# StepperV2.net
KiCad netlist of a schematic drawn in Altium Designer
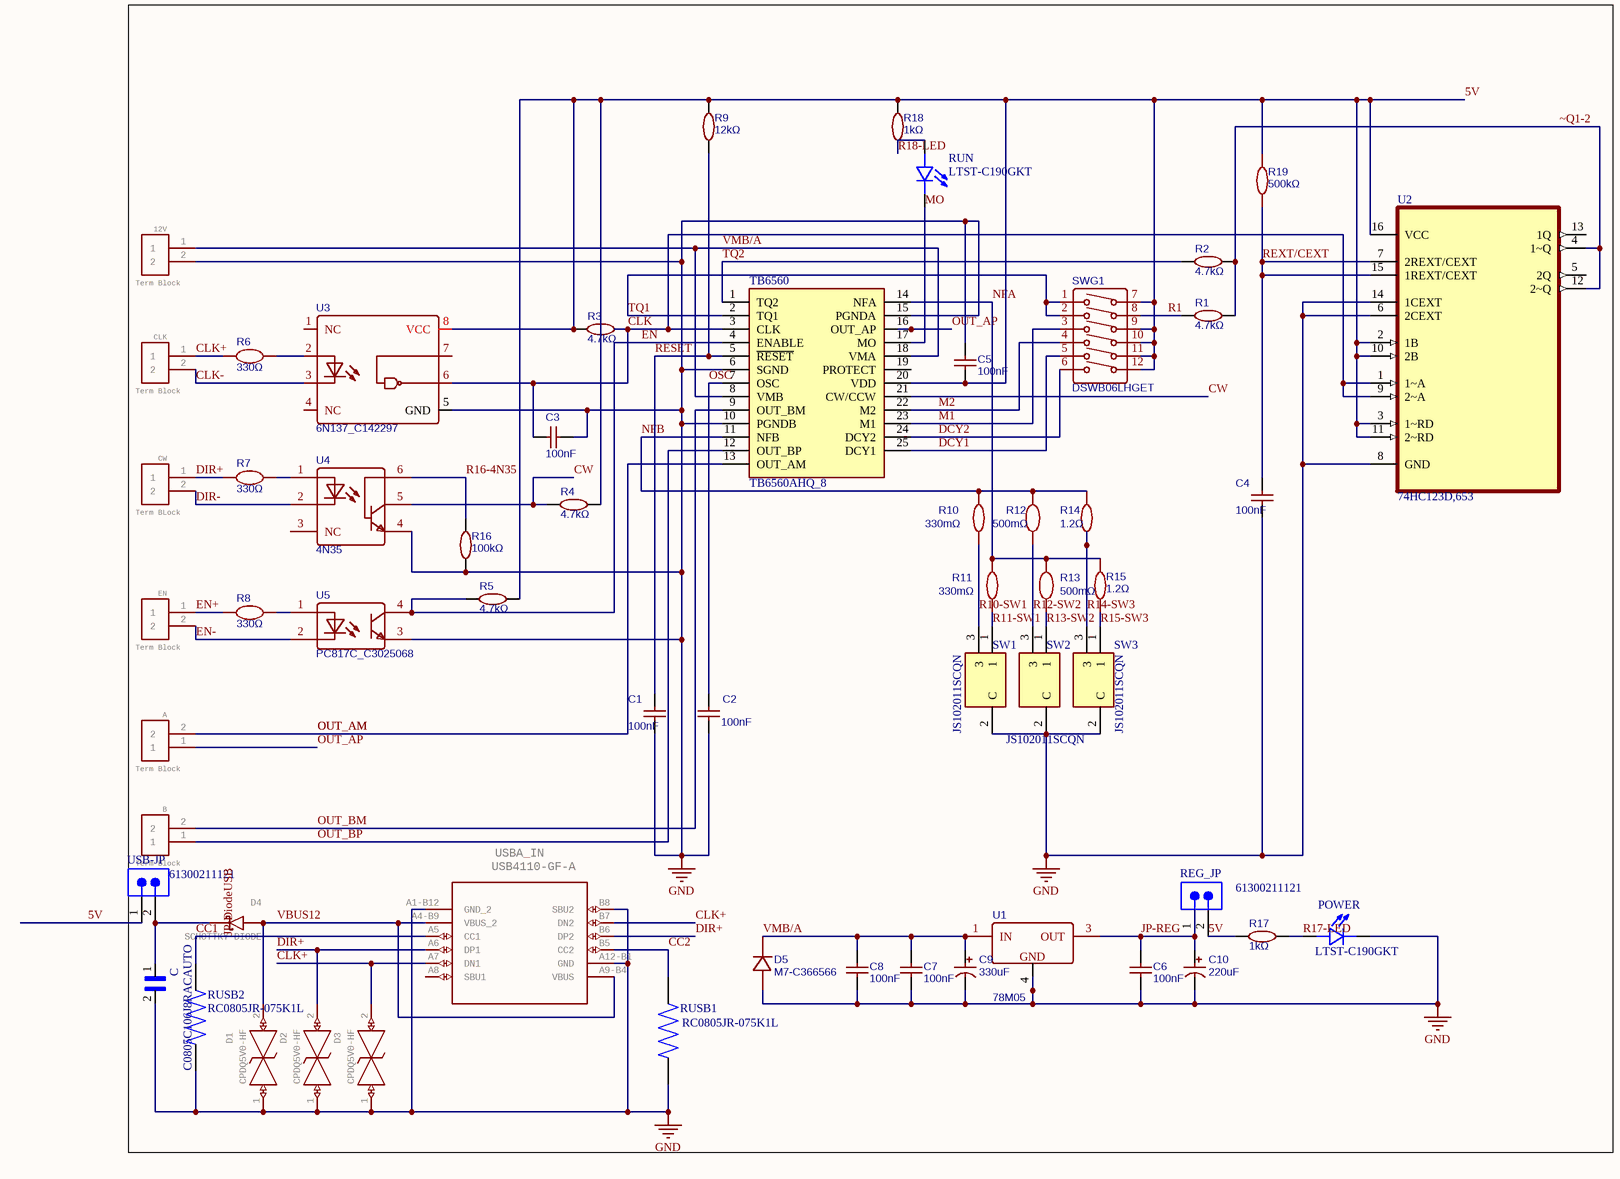
[diagram p0: StepperV2.SchDoc]

(export (version "E")
  (design (tool "Eeschema 10.0.6"))
  (components
    (comp (ref "12V")
      (value "Term Block")
      (footprint "TE_282837-2")
      (fields (field (name "MF") "TE Connectivity") (field (name "MP") "282837-2"))
      (libsource (lib "Terminal_Block2P") (part "282837-2"))
    )
    (comp (ref "A")
      (value "Term Block")
      (footprint "TE_282837-2")
      (fields (field (name "MF") "TE Connectivity") (field (name "MP") "282837-2"))
      (libsource (lib "") (part "282837-2_1"))
    )
    (comp (ref "B")
      (value "Term Block")
      (footprint "TE_282837-2")
      (fields (field (name "MF") "TE Connectivity") (field (name "MP") "282837-2"))
      (libsource (lib "Terminal_Block2P") (part "282837-2"))
    )
    (comp (ref "C")
      (value "C0805C106J8RACAUTO")
      (footprint "C0805C106J8RACAUTO.:CAPC2012X88N")
      (description "10ÂµF Â±5% 10V Ceramic Capacitor X7R 0805 _2012 Metric_")
      (fields (field (name "MF") "KEMET"))
      (libsource (lib "C0805C106J8RACAUTO") (part "C0805C106J8RACAUTO"))
    )
    (comp (ref "C1")
      (value "100nF")
      (footprint "C0805")
      (fields (field (name "MANUFACTURER") "FH(风华)") (field (name "MANUFACTURER PART") "0805B104J500NT"))
      (libsource (lib "0.1uFCAP") (part "100nF"))
    )
    (comp (ref "C2")
      (value "100nF")
      (footprint "C0805")
      (fields (field (name "MANUFACTURER") "FH(风华)") (field (name "MANUFACTURER PART") "0805B104J500NT"))
      (libsource (lib "0.1uFCAP") (part "100nF"))
    )
    (comp (ref "C3")
      (value "100nF")
      (footprint "C0805")
      (fields (field (name "MANUFACTURER") "FH(风华)") (field (name "MANUFACTURER PART") "0805B104J500NT"))
      (libsource (lib "0.1uFCAP") (part "100nF"))
    )
    (comp (ref "C4")
      (value "100nF")
      (footprint "C0805")
      (fields (field (name "MANUFACTURER") "FH(风华)") (field (name "MANUFACTURER PART") "0805B104J500NT"))
      (libsource (lib "0.1uFCAP") (part "100nF"))
    )
    (comp (ref "C5")
      (value "100nF")
      (footprint "C0805")
      (fields (field (name "MANUFACTURER") "FH(风华)") (field (name "MANUFACTURER PART") "0805B104J500NT"))
      (libsource (lib "0.1uFCAP") (part "100nF"))
    )
    (comp (ref "C6")
      (value "100nF")
      (footprint "C0805")
      (fields (field (name "MANUFACTURER") "FH(风华)") (field (name "MANUFACTURER PART") "0805B104J500NT"))
      (libsource (lib "0.1uFCAP") (part "100nF"))
    )
    (comp (ref "C7")
      (value "100nF")
      (footprint "C0805")
      (fields (field (name "MANUFACTURER") "FH(风华)") (field (name "MANUFACTURER PART") "0805B104J500NT"))
      (libsource (lib "0.1uFCAP") (part "100nF"))
    )
    (comp (ref "C8")
      (value "100nF")
      (footprint "C0805")
      (fields (field (name "MANUFACTURER") "FH(风华)") (field (name "MANUFACTURER PART") "0805B104J500NT"))
      (libsource (lib "0.1uFCAP") (part "100nF"))
    )
    (comp (ref "C9")
      (value "330uF")
      (footprint "CAP-TH_BD8.0-P3.50-D0.6-FD")
      (fields
        (field (name "MANUFACTURER") "CX(承兴)")
        (field (name "MANUFACTURER PART") "GR337M050F20RR0VL4FP0")
      )
      (libsource (lib "330uF_CAP") (part "330uF"))
    )
    (comp (ref "C10")
      (value "220uF")
      (footprint "CAP-TH_BD6.3-P2.50-D1.0-FD")
      (fields
        (field (name "MANUFACTURER") "CX(承兴)")
        (field (name "MANUFACTURER PART") "KM227M016E11RR0VH2FP0")
      )
      (libsource (lib "220uF_CAP") (part "220uF"))
    )
    (comp (ref "CLK")
      (value "Term Block")
      (footprint "TE_282837-2")
      (fields (field (name "MF") "TE Connectivity") (field (name "MP") "282837-2"))
      (libsource (lib "Terminal_Block2P") (part "282837-2"))
    )
    (comp (ref "CW")
      (value "Term BLock")
      (footprint "TE_282837-2")
      (fields (field (name "MF") "TE Connectivity") (field (name "MP") "282837-2"))
      (libsource (lib "Terminal_Block2P") (part "282837-2"))
    )
    (comp (ref "D1")
      (value "CPDQ5V0-HF")
      (footprint "MBTB-D-SOD-923F-IMP-0402")
      (fields (field (name "MF") "Comchip Technology"))
      (libsource (lib "CPDQ5V0-HF") (part "CPDQ5V0-HF"))
    )
    (comp (ref "D2")
      (value "CPDQ5V0-HF")
      (footprint "MBTB-D-SOD-923F-IMP-0402")
      (fields (field (name "MF") "Comchip Technology"))
      (libsource (lib "CPDQ5V0-HF") (part "CPDQ5V0-HF"))
    )
    (comp (ref "D3")
      (value "CPDQ5V0-HF")
      (footprint "MBTB-D-SOD-923F-IMP-0402")
      (fields (field (name "MF") "Comchip Technology"))
      (libsource (lib "CPDQ5V0-HF") (part "CPDQ5V0-HF"))
    )
    (comp (ref "D4")
      (value "SCHOTTKY DIODE")
      (footprint "SOD3715X145N")
      (fields (field (name "MF") "Diodes Inc.") (field (name "MP") "1N5819HW-7-F"))
      (libsource (lib "1N5819HW-7-F") (part "1N5819HW-7-F"))
    )
    (comp (ref "D5")
      (value "M7-C366566")
      (footprint "SMAF_L3.5-W2.6-LS4.7-RD")
      (fields
        (field (name "MANUFACTURER") "DOWO(东沃)")
        (field (name "MANUFACTURER PART") "M7")
        (field (name "CONTRIBUTOR") "LCSC")
      )
      (libsource (lib "M7") (part "M7-C366566"))
    )
    (comp (ref "EN")
      (value "Term Block")
      (footprint "TE_282837-2")
      (fields (field (name "MF") "TE Connectivity") (field (name "MP") "282837-2"))
      (libsource (lib "Terminal_Block2P") (part "282837-2"))
    )
    (comp (ref "POWER")
      (value "LTST-C190GKT")
      (footprint "LEDC1608X35N")
      (fields (field (name "MF") "{'manufacturer': u'Lite-On Inc.'}"))
      (libsource (lib "") (part "LTST-C190GKT_1"))
    )
    (comp (ref "R1")
      (value "4.7kΩ")
      (footprint "R0805")
      (fields (field (name "MANUFACTURER") "FH(风华)") (field (name "MANUFACTURER PART") "RS-05K472JT"))
      (libsource (lib "4_7KO") (part "4.7kΩ"))
    )
    (comp (ref "R2")
      (value "4.7kΩ")
      (footprint "R0805")
      (fields (field (name "MANUFACTURER") "FH(风华)") (field (name "MANUFACTURER PART") "RS-05K472JT"))
      (libsource (lib "4_7KO") (part "4.7kΩ"))
    )
    (comp (ref "R3")
      (value "4.7kΩ")
      (footprint "R0805")
      (fields (field (name "MANUFACTURER") "FH(风华)") (field (name "MANUFACTURER PART") "RS-05K472JT"))
      (libsource (lib "4_7KO") (part "4.7kΩ"))
    )
    (comp (ref "R4")
      (value "4.7kΩ")
      (footprint "R0805")
      (fields (field (name "MANUFACTURER") "FH(风华)") (field (name "MANUFACTURER PART") "RS-05K472JT"))
      (libsource (lib "4_7KO") (part "4.7kΩ"))
    )
    (comp (ref "R5")
      (value "4.7kΩ")
      (footprint "R0805")
      (fields (field (name "MANUFACTURER") "FH(风华)") (field (name "MANUFACTURER PART") "RS-05K472JT"))
      (libsource (lib "4_7KO") (part "4.7kΩ"))
    )
    (comp (ref "R6")
      (value "330Ω")
      (footprint "R0805")
      (fields
        (field (name "MANUFACTURER") "EVER OHMS(天二科技)")
        (field (name "MANUFACTURER PART") "CR0805J330RP05Z")
        (field (name "CONTRIBUTOR") "LCSC")
      )
      (libsource (lib "330OHM") (part "330Ω"))
    )
    (comp (ref "R7")
      (value "330Ω")
      (footprint "R0805")
      (fields
        (field (name "MANUFACTURER") "EVER OHMS(天二科技)")
        (field (name "MANUFACTURER PART") "CR0805J330RP05Z")
        (field (name "CONTRIBUTOR") "LCSC")
      )
      (libsource (lib "330OHM") (part "330Ω"))
    )
    (comp (ref "R8")
      (value "330Ω")
      (footprint "R0805")
      (fields
        (field (name "MANUFACTURER") "EVER OHMS(天二科技)")
        (field (name "MANUFACTURER PART") "CR0805J330RP05Z")
        (field (name "CONTRIBUTOR") "LCSC")
      )
      (libsource (lib "330OHM") (part "330Ω"))
    )
    (comp (ref "R9")
      (value "12kΩ")
      (footprint "R0805")
      (fields
        (field (name "MANUFACTURER") "UNI-ROYAL(厚声)")
        (field (name "MANUFACTURER PART") "0805W8J0123T5E")
      )
      (libsource (lib "12kOHM") (part "12kΩ"))
    )
    (comp (ref "R10")
      (value "330mΩ")
      (footprint "R2512")
      (fields
        (field (name "MANUFACTURER") "EVER OHMS(天二科技)")
        (field (name "MANUFACTURER PART") "CRH2512JR330E04Z")
        (field (name "CONTRIBUTOR") "LCSC")
      )
      (libsource (lib "0_33OHM") (part "330mΩ"))
    )
    (comp (ref "R11")
      (value "330mΩ")
      (footprint "R2512")
      (fields
        (field (name "MANUFACTURER") "EVER OHMS(天二科技)")
        (field (name "MANUFACTURER PART") "CRH2512JR330E04Z")
        (field (name "CONTRIBUTOR") "LCSC")
      )
      (libsource (lib "0_33OHM") (part "330mΩ"))
    )
    (comp (ref "R12")
      (value "500mΩ")
      (footprint "R2512")
      (fields
        (field (name "MANUFACTURER") "SEI(Stackpole Electronics Inc.)")
        (field (name "MANUFACTURER PART") "CSRN2512FKR500")
        (field (name "CONTRIBUTOR") "LCSC")
      )
      (libsource (lib "0_5OHM") (part "500mΩ"))
    )
    (comp (ref "R13")
      (value "500mΩ")
      (footprint "R2512")
      (fields
        (field (name "MANUFACTURER") "SEI(Stackpole Electronics Inc.)")
        (field (name "MANUFACTURER PART") "CSRN2512FKR500")
        (field (name "CONTRIBUTOR") "LCSC")
      )
      (libsource (lib "0_5OHM") (part "500mΩ"))
    )
    (comp (ref "R14")
      (value "1.2Ω")
      (footprint "R1210")
      (fields
        (field (name "MANUFACTURER") "EVER OHMS(天二科技)")
        (field (name "MANUFACTURER PART") "CR1210F1R20P05S")
        (field (name "CONTRIBUTOR") "LCSC")
      )
      (libsource (lib "1_2OHM") (part "1.2Ω"))
    )
    (comp (ref "R15")
      (value "1.2Ω")
      (footprint "R1210")
      (fields
        (field (name "MANUFACTURER") "EVER OHMS(天二科技)")
        (field (name "MANUFACTURER PART") "CR1210F1R20P05S")
        (field (name "CONTRIBUTOR") "LCSC")
      )
      (libsource (lib "1_2OHM") (part "1.2Ω"))
    )
    (comp (ref "R16")
      (value "100kΩ")
      (footprint "R0805")
      (fields (field (name "MANUFACTURER") "RALEC(旺诠)") (field (name "MANUFACTURER PART") "RTT05104JTP"))
      (libsource (lib "100KOHM") (part "100kΩ"))
    )
    (comp (ref "R17")
      (value "1kΩ")
      (footprint "R0805")
      (fields (field (name "MANUFACTURER") "YAGEO(国巨)") (field (name "MANUFACTURER PART") "RC0805JR-071KL"))
      (libsource (lib "1kOHM") (part "1kΩ"))
    )
    (comp (ref "R18")
      (value "1kΩ")
      (footprint "R0805")
      (fields (field (name "MANUFACTURER") "YAGEO(国巨)") (field (name "MANUFACTURER PART") "RC0805JR-071KL"))
      (libsource (lib "1kOHM") (part "1kΩ"))
    )
    (comp (ref "R19")
      (value "500kΩ")
      (footprint "R0805")
      (fields
        (field (name "MANUFACTURER") "Viking(光颉)")
        (field (name "MANUFACTURER PART") "AR05BTCW5003")
        (field (name "CONTRIBUTOR") "LCSC")
      )
      (libsource (lib "500KOHM") (part "500kΩ"))
    )
    (comp (ref "REG_JP")
      (value "61300211121")
      (footprint "61300211121")
      (libsource (lib "61300211121") (part "CMP-1712-00002-5"))
    )
    (comp (ref "RUN")
      (value "LTST-C190GKT")
      (footprint "LEDC1608X35N")
      (fields (field (name "MF") "{'manufacturer': u'Lite-On Inc.'}"))
      (libsource (lib "LTST-C190GKT") (part "LTST-C190GKT"))
    )
    (comp (ref "RUSB1")
      (value "RC0805JR-075K1L")
      (footprint "RC0805JR-075K1L:RESC2012X60N")
      (description "RC0805 5,1K 5% 0,125W")
      (libsource (lib "RC0805JR-075K1L") (part "RC0805JR-075K1L"))
    )
    (comp (ref "RUSB2")
      (value "RC0805JR-075K1L")
      (footprint "RC0805JR-075K1L:RESC2012X60N")
      (description "RC0805 5,1K 5% 0,125W")
      (libsource (lib "RC0805JR-075K1L") (part "RC0805JR-075K1L"))
    )
    (comp (ref "SW1")
      (value "JS102011SCQN")
      (footprint "SamacSys:JS102011SCQN")
      (description "Switch")
      (fields (field (name "MOUSER PART NUMBER") "611-JS102011SCQN"))
      (libsource (lib "SSwitch") (part "JS102011SCQN"))
    )
    (comp (ref "SW2")
      (value "JS102011SCQN")
      (footprint "SamacSys:JS102011SCQN")
      (description "Switch")
      (fields (field (name "MOUSER PART NUMBER") "611-JS102011SCQN"))
      (libsource (lib "SSwitch") (part "JS102011SCQN"))
    )
    (comp (ref "SW3")
      (value "JS102011SCQN")
      (footprint "SamacSys:JS102011SCQN")
      (description "Switch")
      (fields (field (name "MOUSER PART NUMBER") "611-JS102011SCQN"))
      (libsource (lib "SSwitch") (part "JS102011SCQN"))
    )
    (comp (ref "SWG1")
      (value "DSWB06LHGET")
      (footprint "SW-TH_DSWB06LHGET")
      (fields (field (name "MANUFACTURER") "YE") (field (name "CONTRIBUTOR") "LCSC"))
      (libsource (lib "DSWB06LHGET") (part "DSWB06LHGET"))
    )
    (comp (ref "TB6560")
      (value "TB6560AHQ_8")
      (footprint "TO127P530X3650X1770-25P")
      (description "Motor / Motion / Ignition Controllers & Drivers Stepping Motor Driver IC")
      (fields (field (name "MANUFACTURER_PART_NUMBER") "TB6560AHQ,8"))
      (libsource (lib "TB6560AHQ_8") (part "TB6560AHQ_8"))
    )
    (comp (ref "U1")
      (value "78M05")
      (footprint "TO-252-2_L6.5-W6.1-P4.58-LS10.0-TL")
      (fields (field (name "MANUFACTURER") "SHIKUES(时科)"))
      (libsource (lib "78M05") (part "78M05"))
    )
    (comp (ref "U2")
      (value "74HC123D,653")
      (footprint "SOIC127P600X175-16N")
      (description "Monostable Multivibrator 65ns 16-SO")
      (fields (field (name "MF") "Nexperia USA") (field (name "DIGI-KEY_PART_NUMBER") "1727-2778-1-ND"))
      (libsource (lib "74HC123D,653") (part "74HC123D,653"))
    )
    (comp (ref "U3")
      (value "6N137_C142297")
      (footprint "DIP-8_L9.8-W6.6-P2.54-LS7.6-BL")
      (fields
        (field (name "MANUFACTURER") "EVERLIGHT(亿光)")
        (field (name "MANUFACTURER PART") "6N137")
        (field (name "CONTRIBUTOR") "LCSC")
      )
      (libsource (lib "6N137") (part "6N137_C142297"))
    )
    (comp (ref "U4")
      (value "4N35")
      (footprint "DIP-6_L8.5-W6.4-P2.54-LS7.6-BL")
      (fields (field (name "MANUFACTURER") "EVERLIGHT(亿光)"))
      (libsource (lib "4N35") (part "4N35"))
    )
    (comp (ref "U5")
      (value "PC817C_C3025068")
      (footprint "DIP-4_L4.6-W6.5-P2.54-LS7.6-BL")
      (fields
        (field (name "MANUFACTURER") "GOODWORK(固得沃克)")
        (field (name "MANUFACTURER PART") "PC817C")
        (field (name "CONTRIBUTOR") "lcsc")
      )
      (libsource (lib "PC817C") (part "PC817C_C3025068"))
    )
    (comp (ref "USB-JP")
      (value "61300211121")
      (footprint "61300211121")
      (libsource (lib "61300211121") (part "CMP-1712-00002-5"))
    )
    (comp (ref "USBA_IN")
      (value "USB4110-GF-A")
      (footprint "USB4110-GF-A_GCT")
      (fields (field (name "COPYRIGHT") "Copyright (C) 2023 Ultra Librarian. All rights reserved."))
      (libsource (lib "USB4110-GF-A") (part "USB4110-GF-A"))
    )
  )
  (nets
    (net (code "1") (name "/5V") (class "Default")
      (node (ref "C5") (pin "1") (pinfunction "1_1") (pintype "passive"))
      (node (ref "R17") (pin "1") (pinfunction "1_1") (pintype "passive"))
      (node (ref "R18") (pin "2") (pinfunction "2_2") (pintype "passive"))
      (node (ref "R19") (pin "2") (pinfunction "2_2") (pintype "passive"))
      (node (ref "R3") (pin "1") (pinfunction "1_1") (pintype "passive"))
      (node (ref "R4") (pin "2") (pinfunction "2_2") (pintype "passive"))
      (node (ref "R5") (pin "2") (pinfunction "2_2") (pintype "passive"))
      (node (ref "R9") (pin "2") (pinfunction "2_2") (pintype "passive"))
      (node (ref "REG_JP") (pin "2") (pinfunction "2_2") (pintype "passive"))
      (node (ref "SWG1") (pin "10") (pinfunction "10_10") (pintype "passive"))
      (node (ref "SWG1") (pin "11") (pinfunction "11_11") (pintype "passive"))
      (node (ref "SWG1") (pin "12") (pinfunction "12_12") (pintype "passive"))
      (node (ref "SWG1") (pin "7") (pinfunction "7_7") (pintype "passive"))
      (node (ref "SWG1") (pin "9") (pinfunction "9_9") (pintype "passive"))
      (node (ref "TB6560") (pin "20") (pinfunction "VDD_20") (pintype "passive"))
      (node (ref "U2") (pin "10") (pinfunction "2B_10") (pintype "input"))
      (node (ref "U2") (pin "11") (pinfunction "2~RD_11") (pintype "input"))
      (node (ref "U2") (pin "16") (pinfunction "VCC_16") (pintype "power_in"))
      (node (ref "U2") (pin "2") (pinfunction "1B_2") (pintype "input"))
      (node (ref "U2") (pin "3") (pinfunction "1~RD_3") (pintype "input"))
      (node (ref "U3") (pin "8") (pinfunction "VCC_8") (pintype "passive"))
      (node (ref "USB-JP") (pin "1") (pinfunction "1_1") (pintype "passive"))
    )
    (net (code "2") (name "/CC1") (class "Default")
      (node (ref "RUSB2") (pin "2") (pinfunction "2_2") (pintype "passive"))
      (node (ref "USBA_IN") (pin "A5") (pinfunction "CC1_A5") (pintype "bidirectional"))
    )
    (net (code "3") (name "/CC2") (class "Default")
      (node (ref "RUSB1") (pin "2") (pinfunction "2_2") (pintype "passive"))
      (node (ref "USBA_IN") (pin "B5") (pinfunction "CC2_B5") (pintype "bidirectional"))
    )
    (net (code "4") (name "/CLK") (class "Default")
      (node (ref "C3") (pin "1") (pinfunction "1_1") (pintype "passive"))
      (node (ref "R3") (pin "2") (pinfunction "2_2") (pintype "passive"))
      (node (ref "TB6560") (pin "3") (pinfunction "CLK_3") (pintype "passive"))
      (node (ref "U2") (pin "1") (pinfunction "1~A_1") (pintype "input"))
      (node (ref "U2") (pin "9") (pinfunction "2~A_9") (pintype "input"))
      (node (ref "U3") (pin "6") (pinfunction "VOUT_6") (pintype "passive"))
    )
    (net (code "5") (name "/CLK+") (class "Default")
      (node (ref "CLK") (pin "1") (pinfunction "1_1") (pintype "passive"))
      (node (ref "D3") (pin "2") (pinfunction "A_2") (pintype "bidirectional"))
      (node (ref "R6") (pin "1") (pinfunction "1_1") (pintype "passive"))
      (node (ref "USBA_IN") (pin "A7") (pinfunction "DN1_A7") (pintype "bidirectional"))
      (node (ref "USBA_IN") (pin "B7") (pinfunction "DN2_B7") (pintype "bidirectional"))
    )
    (net (code "6") (name "/CLK-") (class "Default")
      (node (ref "CLK") (pin "2") (pinfunction "2_2") (pintype "passive"))
      (node (ref "U3") (pin "3") (pinfunction "CAT_3") (pintype "passive"))
    )
    (net (code "7") (name "/CW") (class "Default")
      (node (ref "R4") (pin "1") (pinfunction "1_1") (pintype "passive"))
      (node (ref "TB6560") (pin "21") (pinfunction "CW/CCW_21") (pintype "passive"))
      (node (ref "U4") (pin "5") (pinfunction "5_5") (pintype "passive"))
    )
    (net (code "8") (name "/DCY1") (class "Default")
      (node (ref "SWG1") (pin "5") (pinfunction "5_5") (pintype "passive"))
      (node (ref "TB6560") (pin "25") (pinfunction "DCY1_25") (pintype "passive"))
    )
    (net (code "9") (name "/DCY2") (class "Default")
      (node (ref "SWG1") (pin "6") (pinfunction "6_6") (pintype "passive"))
      (node (ref "TB6560") (pin "24") (pinfunction "DCY2_24") (pintype "passive"))
    )
    (net (code "10") (name "/DIR+") (class "Default")
      (node (ref "CW") (pin "1") (pinfunction "1_1") (pintype "passive"))
      (node (ref "D2") (pin "2") (pinfunction "A_2") (pintype "bidirectional"))
      (node (ref "R7") (pin "1") (pinfunction "1_1") (pintype "passive"))
      (node (ref "USBA_IN") (pin "A6") (pinfunction "DP1_A6") (pintype "bidirectional"))
      (node (ref "USBA_IN") (pin "B6") (pinfunction "DP2_B6") (pintype "bidirectional"))
    )
    (net (code "11") (name "/DIR-") (class "Default")
      (node (ref "CW") (pin "2") (pinfunction "2_2") (pintype "passive"))
      (node (ref "U4") (pin "2") (pinfunction "2_2") (pintype "passive"))
    )
    (net (code "12") (name "/EN") (class "Default")
      (node (ref "R5") (pin "1") (pinfunction "1_1") (pintype "passive"))
      (node (ref "TB6560") (pin "4") (pinfunction "ENABLE_4") (pintype "passive"))
      (node (ref "U5") (pin "4") (pinfunction "COL_4") (pintype "passive"))
    )
    (net (code "13") (name "/EN+") (class "Default")
      (node (ref "EN") (pin "1") (pinfunction "1_1") (pintype "passive"))
      (node (ref "R8") (pin "1") (pinfunction "1_1") (pintype "passive"))
    )
    (net (code "14") (name "/EN-") (class "Default")
      (node (ref "EN") (pin "2") (pinfunction "2_2") (pintype "passive"))
      (node (ref "U5") (pin "2") (pinfunction "CAT_2") (pintype "passive"))
    )
    (net (code "15") (name "/JP-REG") (class "Default")
      (node (ref "C10") (pin "1") (pinfunction "1_1") (pintype "passive"))
      (node (ref "C6") (pin "2") (pinfunction "2_2") (pintype "passive"))
      (node (ref "REG_JP") (pin "1") (pinfunction "1_1") (pintype "passive"))
      (node (ref "U1") (pin "3") (pinfunction "OUT_3") (pintype "passive"))
    )
    (net (code "16") (name "/M1") (class "Default")
      (node (ref "SWG1") (pin "3") (pinfunction "3_3") (pintype "passive"))
      (node (ref "TB6560") (pin "23") (pinfunction "M1_23") (pintype "passive"))
    )
    (net (code "17") (name "/M2") (class "Default")
      (node (ref "SWG1") (pin "4") (pinfunction "4_4") (pintype "passive"))
      (node (ref "TB6560") (pin "22") (pinfunction "M2_22") (pintype "passive"))
    )
    (net (code "18") (name "/MO") (class "Default")
      (node (ref "RUN") (pin "C") (pinfunction "C_C") (pintype "passive"))
      (node (ref "TB6560") (pin "17") (pinfunction "MO_17") (pintype "passive"))
    )
    (net (code "19") (name "/NFA") (class "Default")
      (node (ref "R11") (pin "2") (pinfunction "2_2") (pintype "passive"))
      (node (ref "R13") (pin "2") (pinfunction "2_2") (pintype "passive"))
      (node (ref "R15") (pin "2") (pinfunction "2_2") (pintype "passive"))
      (node (ref "TB6560") (pin "14") (pinfunction "NFA_14") (pintype "passive"))
    )
    (net (code "20") (name "/NFB") (class "Default")
      (node (ref "R10") (pin "2") (pinfunction "2_2") (pintype "passive"))
      (node (ref "R12") (pin "2") (pinfunction "2_2") (pintype "passive"))
      (node (ref "R14") (pin "2") (pinfunction "2_2") (pintype "passive"))
      (node (ref "TB6560") (pin "11") (pinfunction "NFB_11") (pintype "passive"))
    )
    (net (code "21") (name "/OSC") (class "Default")
      (node (ref "C2") (pin "1") (pinfunction "1_1") (pintype "passive"))
      (node (ref "TB6560") (pin "7") (pinfunction "OSC_7") (pintype "passive"))
    )
    (net (code "22") (name "/OUT_AM") (class "Default")
      (node (ref "A") (pin "2") (pinfunction "2_2") (pintype "passive"))
      (node (ref "TB6560") (pin "13") (pinfunction "OUT_AM_13") (pintype "passive"))
    )
    (net (code "23") (name "/OUT_AP") (class "Default")
      (node (ref "A") (pin "1") (pinfunction "1_1") (pintype "passive"))
      (node (ref "TB6560") (pin "16") (pinfunction "OUT_AP_16") (pintype "passive"))
    )
    (net (code "24") (name "/OUT_BM") (class "Default")
      (node (ref "B") (pin "2") (pinfunction "2_2") (pintype "passive"))
      (node (ref "TB6560") (pin "9") (pinfunction "OUT_BM_9") (pintype "passive"))
    )
    (net (code "25") (name "/OUT_BP") (class "Default")
      (node (ref "B") (pin "1") (pinfunction "1_1") (pintype "passive"))
      (node (ref "TB6560") (pin "12") (pinfunction "OUT_BP_12") (pintype "passive"))
    )
    (net (code "26") (name "/R1") (class "Default")
      (node (ref "R1") (pin "1") (pinfunction "1_1") (pintype "passive"))
      (node (ref "SWG1") (pin "8") (pinfunction "8_8") (pintype "passive"))
    )
    (net (code "27") (name "/R10-SW1") (class "Default")
      (node (ref "R10") (pin "1") (pinfunction "1_1") (pintype "passive"))
      (node (ref "SW1") (pin "3") (pinfunction "3_3") (pintype "passive"))
    )
    (net (code "28") (name "/R11-SW1") (class "Default")
      (node (ref "R11") (pin "1") (pinfunction "1_1") (pintype "passive"))
      (node (ref "SW1") (pin "1") (pinfunction "1_1") (pintype "passive"))
    )
    (net (code "29") (name "/R12-SW2") (class "Default")
      (node (ref "R12") (pin "1") (pinfunction "1_1") (pintype "passive"))
      (node (ref "SW2") (pin "3") (pinfunction "3_3") (pintype "passive"))
    )
    (net (code "30") (name "/R13-SW2") (class "Default")
      (node (ref "R13") (pin "1") (pinfunction "1_1") (pintype "passive"))
      (node (ref "SW2") (pin "1") (pinfunction "1_1") (pintype "passive"))
    )
    (net (code "31") (name "/R14-SW3") (class "Default")
      (node (ref "R14") (pin "1") (pinfunction "1_1") (pintype "passive"))
      (node (ref "SW3") (pin "3") (pinfunction "3_3") (pintype "passive"))
    )
    (net (code "32") (name "/R15-SW3") (class "Default")
      (node (ref "R15") (pin "1") (pinfunction "1_1") (pintype "passive"))
      (node (ref "SW3") (pin "1") (pinfunction "1_1") (pintype "passive"))
    )
    (net (code "33") (name "/R16-4N35") (class "Default")
      (node (ref "R16") (pin "2") (pinfunction "2_2") (pintype "passive"))
      (node (ref "U4") (pin "6") (pinfunction "6_6") (pintype "passive"))
    )
    (net (code "34") (name "/R17-LED") (class "Default")
      (node (ref "POWER") (pin "A") (pinfunction "A_A") (pintype "passive"))
      (node (ref "R17") (pin "2") (pinfunction "2_2") (pintype "passive"))
    )
    (net (code "35") (name "/R18-LED") (class "Default")
      (node (ref "R18") (pin "1") (pinfunction "1_1") (pintype "passive"))
      (node (ref "RUN") (pin "A") (pinfunction "A_A") (pintype "passive"))
    )
    (net (code "36") (name "/RESET") (class "Default")
      (node (ref "C1") (pin "2") (pinfunction "2_2") (pintype "passive"))
      (node (ref "R9") (pin "1") (pinfunction "1_1") (pintype "passive"))
      (node (ref "TB6560") (pin "5") (pinfunction "~{RESET}_5") (pintype "passive"))
    )
    (net (code "37") (name "/REXT{slash}CEXT") (class "Default")
      (node (ref "C4") (pin "2") (pinfunction "2_2") (pintype "passive"))
      (node (ref "R19") (pin "1") (pinfunction "1_1") (pintype "passive"))
      (node (ref "U2") (pin "15") (pinfunction "1REXT/CEXT_15") (pintype "passive"))
      (node (ref "U2") (pin "7") (pinfunction "2REXT/CEXT_7") (pintype "passive"))
    )
    (net (code "38") (name "/TQ1") (class "Default")
      (node (ref "SWG1") (pin "1") (pinfunction "1_1") (pintype "passive"))
      (node (ref "SWG1") (pin "2") (pinfunction "2_2") (pintype "passive"))
      (node (ref "TB6560") (pin "2") (pinfunction "TQ1_2") (pintype "passive"))
    )
    (net (code "39") (name "/TQ2") (class "Default")
      (node (ref "R2") (pin "1") (pinfunction "1_1") (pintype "passive"))
      (node (ref "TB6560") (pin "1") (pinfunction "TQ2_1") (pintype "passive"))
    )
    (net (code "40") (name "/VBUS12") (class "Default")
      (node (ref "D1") (pin "2") (pinfunction "A_2") (pintype "bidirectional"))
      (node (ref "D4") (pin "A") (pinfunction "A_A") (pintype "passive"))
      (node (ref "USBA_IN") (pin "A4-B9") (pinfunction "VBUS_2_A4-B9") (pintype "power_in"))
      (node (ref "USBA_IN") (pin "A9-B4") (pinfunction "VBUS_A9-B4") (pintype "power_in"))
    )
    (net (code "41") (name "/VMB{slash}A") (class "Default")
      (node (ref "12V") (pin "1") (pinfunction "1_1") (pintype "passive"))
      (node (ref "C7") (pin "2") (pinfunction "2_2") (pintype "passive"))
      (node (ref "C8") (pin "2") (pinfunction "2_2") (pintype "passive"))
      (node (ref "C9") (pin "1") (pinfunction "1_1") (pintype "passive"))
      (node (ref "D5") (pin "1") (pinfunction "C_1") (pintype "passive"))
      (node (ref "TB6560") (pin "18") (pinfunction "VMA_18") (pintype "passive"))
      (node (ref "TB6560") (pin "8") (pinfunction "VMB_8") (pintype "passive"))
      (node (ref "U1") (pin "1") (pinfunction "IN_1") (pintype "passive"))
    )
    (net (code "42") (name "/~Q1-2") (class "Default")
      (node (ref "R1") (pin "2") (pinfunction "2_2") (pintype "passive"))
      (node (ref "R2") (pin "2") (pinfunction "2_2") (pintype "passive"))
      (node (ref "U2") (pin "12") (pinfunction "2~Q_12") (pintype "output"))
      (node (ref "U2") (pin "4") (pinfunction "1~Q_4") (pintype "output"))
    )
    (net (code "43") (name "GND") (class "Default")
      (node (ref "12V") (pin "2") (pinfunction "2_2") (pintype "passive"))
      (node (ref "C") (pin "2") (pinfunction "2_2") (pintype "passive"))
      (node (ref "C1") (pin "1") (pinfunction "1_1") (pintype "passive"))
      (node (ref "C10") (pin "2") (pinfunction "2_2") (pintype "passive"))
      (node (ref "C2") (pin "2") (pinfunction "2_2") (pintype "passive"))
      (node (ref "C3") (pin "2") (pinfunction "2_2") (pintype "passive"))
      (node (ref "C4") (pin "1") (pinfunction "1_1") (pintype "passive"))
      (node (ref "C5") (pin "2") (pinfunction "2_2") (pintype "passive"))
      (node (ref "C6") (pin "1") (pinfunction "1_1") (pintype "passive"))
      (node (ref "C7") (pin "1") (pinfunction "1_1") (pintype "passive"))
      (node (ref "C8") (pin "1") (pinfunction "1_1") (pintype "passive"))
      (node (ref "C9") (pin "2") (pinfunction "2_2") (pintype "passive"))
      (node (ref "D1") (pin "1") (pinfunction "K_1") (pintype "bidirectional"))
      (node (ref "D2") (pin "1") (pinfunction "K_1") (pintype "bidirectional"))
      (node (ref "D3") (pin "1") (pinfunction "K_1") (pintype "bidirectional"))
      (node (ref "D5") (pin "2") (pinfunction "A_2") (pintype "passive"))
      (node (ref "POWER") (pin "C") (pinfunction "C_C") (pintype "passive"))
      (node (ref "R16") (pin "1") (pinfunction "1_1") (pintype "passive"))
      (node (ref "RUSB1") (pin "1") (pinfunction "1_1") (pintype "passive"))
      (node (ref "RUSB2") (pin "1") (pinfunction "1_1") (pintype "passive"))
      (node (ref "SW1") (pin "2") (pinfunction "C_2") (pintype "passive"))
      (node (ref "SW2") (pin "2") (pinfunction "C_2") (pintype "passive"))
      (node (ref "SW3") (pin "2") (pinfunction "C_2") (pintype "passive"))
      (node (ref "TB6560") (pin "10") (pinfunction "PGNDB_10") (pintype "passive"))
      (node (ref "TB6560") (pin "15") (pinfunction "PGNDA_15") (pintype "passive"))
      (node (ref "TB6560") (pin "6") (pinfunction "SGND_6") (pintype "passive"))
      (node (ref "U1") (pin "4") (pinfunction "GND_4") (pintype "passive"))
      (node (ref "U2") (pin "14") (pinfunction "1CEXT_14") (pintype "passive"))
      (node (ref "U2") (pin "6") (pinfunction "2CEXT_6") (pintype "passive"))
      (node (ref "U2") (pin "8") (pinfunction "GND_8") (pintype "passive"))
      (node (ref "U3") (pin "5") (pinfunction "GND_5") (pintype "passive"))
      (node (ref "U4") (pin "4") (pinfunction "4_4") (pintype "passive"))
      (node (ref "U5") (pin "3") (pinfunction "EM_3") (pintype "passive"))
      (node (ref "USBA_IN") (pin "A1-B12") (pinfunction "GND_2_A1-B12") (pintype "passive"))
      (node (ref "USBA_IN") (pin "A12-B1") (pinfunction "GND_A12-B1") (pintype "passive"))
      (node (ref "USBA_IN") (pin "B8") (pinfunction "SBU2_B8") (pintype "bidirectional"))
    )
    (net (code "44") (name "Net-(D4-K)") (class "Default")
      (node (ref "C") (pin "1") (pinfunction "1_1") (pintype "passive"))
      (node (ref "D4") (pin "C") (pinfunction "K_C") (pintype "passive"))
      (node (ref "USB-JP") (pin "2") (pinfunction "2_2") (pintype "passive"))
    )
    (net (code "45") (name "Net-(R7-Pad2)") (class "Default")
      (node (ref "R7") (pin "2") (pinfunction "2_2") (pintype "passive"))
      (node (ref "U4") (pin "1") (pinfunction "1_1") (pintype "passive"))
    )
    (net (code "46") (name "Net-(U3-AN)") (class "Default")
      (node (ref "R6") (pin "2") (pinfunction "2_2") (pintype "passive"))
      (node (ref "U3") (pin "2") (pinfunction "AN_2") (pintype "passive"))
    )
    (net (code "47") (name "Net-(U5-AN)") (class "Default")
      (node (ref "R8") (pin "2") (pinfunction "2_2") (pintype "passive"))
      (node (ref "U5") (pin "1") (pinfunction "AN_1") (pintype "passive"))
    )
    (net (code "48") (name "unconnected-(TB6560-PROTECT-Pad19)") (class "Default")
      (node (ref "TB6560") (pin "19") (pinfunction "PROTECT_19") (pintype "passive"))
    )
    (net (code "49") (name "unconnected-(U2-1Q-Pad13)") (class "Default")
      (node (ref "U2") (pin "13") (pinfunction "1Q_13") (pintype "output"))
    )
    (net (code "50") (name "unconnected-(U2-2Q-Pad5)") (class "Default")
      (node (ref "U2") (pin "5") (pinfunction "2Q_5") (pintype "output"))
    )
    (net (code "51") (name "unconnected-(U3-NC-Pad1)") (class "Default")
      (node (ref "U3") (pin "1") (pinfunction "NC_1") (pintype "passive"))
    )
    (net (code "52") (name "unconnected-(U3-NC-Pad4)") (class "Default")
      (node (ref "U3") (pin "4") (pinfunction "NC_4") (pintype "passive"))
    )
    (net (code "53") (name "unconnected-(U3-VE-Pad7)") (class "Default")
      (node (ref "U3") (pin "7") (pinfunction "VE_7") (pintype "passive"))
    )
    (net (code "54") (name "unconnected-(U4-NC-Pad3)") (class "Default")
      (node (ref "U4") (pin "3") (pinfunction "NC_3") (pintype "passive"))
    )
    (net (code "55") (name "unconnected-(USBA_IN-SBU1-PadA8)") (class "Default")
      (node (ref "USBA_IN") (pin "A8") (pinfunction "SBU1_A8") (pintype "bidirectional"))
    )
  )
)
